# ax12_control_board.net
KiCad netlist of a schematic drawn in EAGLE
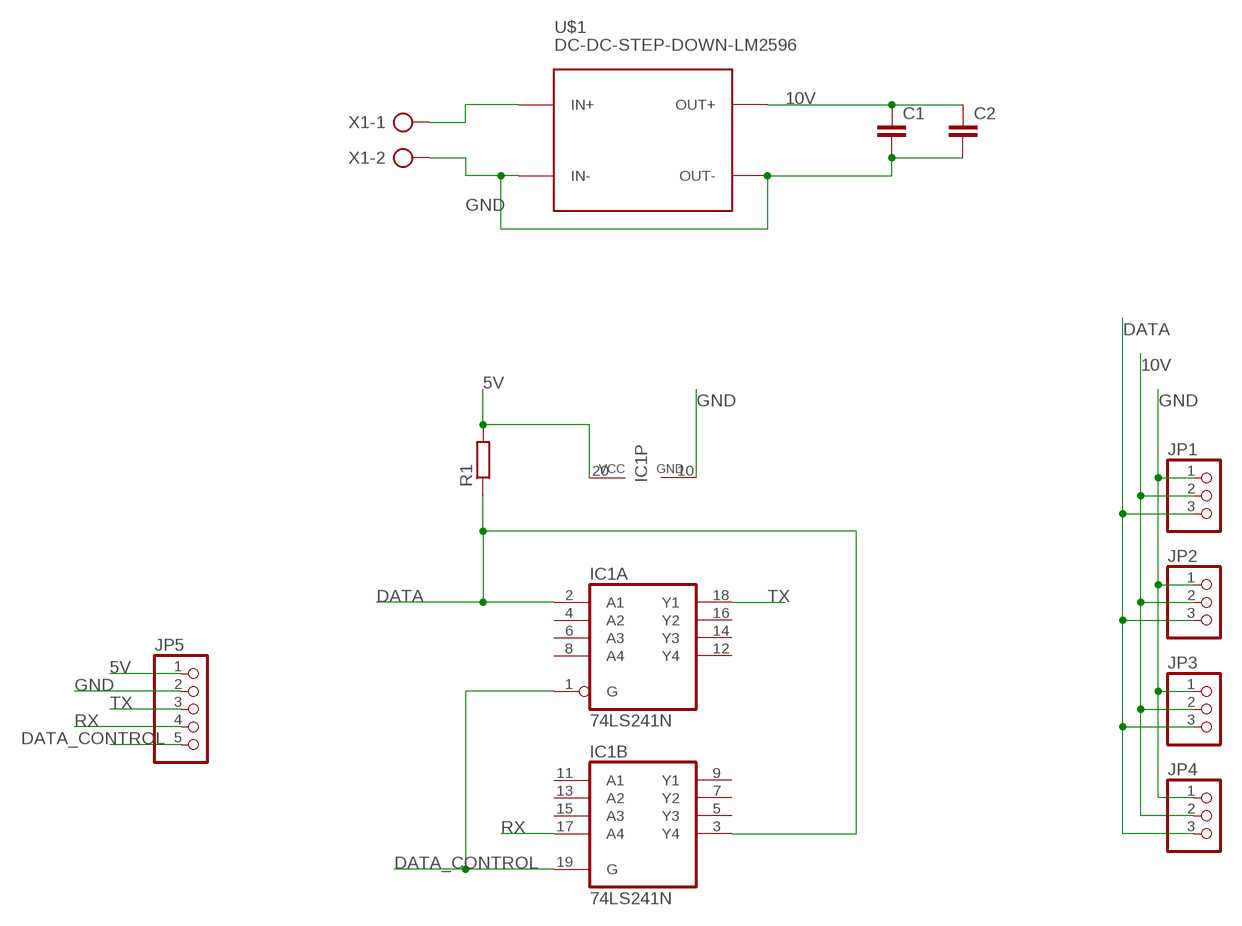
[diagram p0: schematic, sheet 1]

(export (version "E")
  (design (tool "Eeschema 10.0.6"))
  (components
    (comp (ref "C1")
      (value "C-EU025-060X050")
      (footprint "eagle-import:C025-060X050")
      (libsource (lib "eagle-import") (part "C-EU025-060X050"))
    )
    (comp (ref "C2")
      (value "C-EU025-060X050")
      (footprint "eagle-import:C025-060X050")
      (libsource (lib "eagle-import") (part "C-EU025-060X050"))
    )
    (comp (ref "IC1")
      (value "74LS241N")
      (footprint "eagle-import:DIL20")
      (libsource (lib "eagle-import") (part "74241NLS"))
    )
    (comp (ref "JP1")
      (value "PINHD-1X3")
      (footprint "eagle-import:1X03")
      (libsource (lib "eagle-import") (part "PINHD-1X3"))
    )
    (comp (ref "JP2")
      (value "PINHD-1X3")
      (footprint "eagle-import:1X03")
      (libsource (lib "eagle-import") (part "PINHD-1X3"))
    )
    (comp (ref "JP3")
      (value "PINHD-1X3")
      (footprint "eagle-import:1X03")
      (libsource (lib "eagle-import") (part "PINHD-1X3"))
    )
    (comp (ref "JP4")
      (value "PINHD-1X3")
      (footprint "eagle-import:1X03")
      (libsource (lib "eagle-import") (part "PINHD-1X3"))
    )
    (comp (ref "JP5")
      (value "PINHD-1X5")
      (footprint "eagle-import:1X05")
      (libsource (lib "eagle-import") (part "PINHD-1X5"))
    )
    (comp (ref "R1")
      (value "R-EU_0207/12")
      (footprint "eagle-import:0207_12")
      (libsource (lib "eagle-import") (part "R-EU_0207/12"))
    )
    (comp (ref "U$1")
      (value "DC-DC-STEP-DOWN-LM2596")
      (footprint "eagle-import:DC-DC-STEP-DOWN-LM2596")
      (libsource (lib "eagle-import") (part "DC-DC-STEP-DOWN-LM2596"))
    )
    (comp (ref "X1")
      (value "AK300/2")
      (footprint "eagle-import:AK300_2")
      (libsource (lib "eagle-import") (part "AK300/2"))
    )
  )
  (nets
    (net (code "1") (name "/5V") (class "Default")
      (node (ref "IC1") (pin "20") (pinfunction "VCC_20") (pintype "power_in"))
      (node (ref "JP5") (pin "1") (pinfunction "1_1") (pintype "passive"))
      (node (ref "R1") (pin "2") (pinfunction "2_2") (pintype "passive"))
    )
    (net (code "2") (name "/10V") (class "Default")
      (node (ref "C1") (pin "1") (pinfunction "1_1") (pintype "passive"))
      (node (ref "C2") (pin "1") (pinfunction "1_1") (pintype "passive"))
      (node (ref "JP1") (pin "2") (pinfunction "2_2") (pintype "passive"))
      (node (ref "JP2") (pin "2") (pinfunction "2_2") (pintype "passive"))
      (node (ref "JP3") (pin "2") (pinfunction "2_2") (pintype "passive"))
      (node (ref "JP4") (pin "2") (pinfunction "2_2") (pintype "passive"))
      (node (ref "U$1") (pin "OUT+") (pinfunction "OUT+_OUT+") (pintype "bidirectional"))
    )
    (net (code "3") (name "/DATA") (class "Default")
      (node (ref "IC1") (pin "2") (pinfunction "A1_2") (pintype "input"))
      (node (ref "IC1") (pin "3") (pinfunction "Y4_3") (pintype "tri_state"))
      (node (ref "JP1") (pin "3") (pinfunction "3_3") (pintype "passive"))
      (node (ref "JP2") (pin "3") (pinfunction "3_3") (pintype "passive"))
      (node (ref "JP3") (pin "3") (pinfunction "3_3") (pintype "passive"))
      (node (ref "JP4") (pin "3") (pinfunction "3_3") (pintype "passive"))
      (node (ref "R1") (pin "1") (pinfunction "1_1") (pintype "passive"))
    )
    (net (code "4") (name "/DATA_CONTROL") (class "Default")
      (node (ref "IC1") (pin "1") (pinfunction "G_1") (pintype "input"))
      (node (ref "IC1") (pin "19") (pinfunction "G_19") (pintype "input"))
      (node (ref "JP5") (pin "5") (pinfunction "5_5") (pintype "passive"))
    )
    (net (code "5") (name "/GND") (class "Default")
      (node (ref "C1") (pin "2") (pinfunction "2_2") (pintype "passive"))
      (node (ref "C2") (pin "2") (pinfunction "2_2") (pintype "passive"))
      (node (ref "IC1") (pin "10") (pinfunction "GND_10") (pintype "power_in"))
      (node (ref "JP1") (pin "1") (pinfunction "1_1") (pintype "passive"))
      (node (ref "JP2") (pin "1") (pinfunction "1_1") (pintype "passive"))
      (node (ref "JP3") (pin "1") (pinfunction "1_1") (pintype "passive"))
      (node (ref "JP4") (pin "1") (pinfunction "1_1") (pintype "passive"))
      (node (ref "JP5") (pin "2") (pinfunction "2_2") (pintype "passive"))
      (node (ref "U$1") (pin "IN-") (pinfunction "IN-_IN-") (pintype "bidirectional"))
      (node (ref "U$1") (pin "OUT-") (pinfunction "OUT-_OUT-") (pintype "bidirectional"))
      (node (ref "X1") (pin "2") (pinfunction "KL_2") (pintype "passive"))
    )
    (net (code "6") (name "/RX") (class "Default")
      (node (ref "IC1") (pin "17") (pinfunction "A4_17") (pintype "input"))
      (node (ref "JP5") (pin "4") (pinfunction "4_4") (pintype "passive"))
    )
    (net (code "7") (name "/TX") (class "Default")
      (node (ref "IC1") (pin "18") (pinfunction "Y1_18") (pintype "tri_state"))
      (node (ref "JP5") (pin "3") (pinfunction "3_3") (pintype "passive"))
    )
    (net (code "8") (name "Net-(X1A-KL)") (class "Default")
      (node (ref "U$1") (pin "IN+") (pinfunction "IN+_IN+") (pintype "bidirectional"))
      (node (ref "X1") (pin "1") (pinfunction "KL_1") (pintype "passive"))
    )
    (net (code "9") (name "unconnected-(IC1A-A2-Pad4)") (class "Default")
      (node (ref "IC1") (pin "4") (pinfunction "A2_4") (pintype "input"))
    )
    (net (code "10") (name "unconnected-(IC1A-A3-Pad6)") (class "Default")
      (node (ref "IC1") (pin "6") (pinfunction "A3_6") (pintype "input"))
    )
    (net (code "11") (name "unconnected-(IC1A-A4-Pad8)") (class "Default")
      (node (ref "IC1") (pin "8") (pinfunction "A4_8") (pintype "input"))
    )
    (net (code "12") (name "unconnected-(IC1A-Y2-Pad16)") (class "Default")
      (node (ref "IC1") (pin "16") (pinfunction "Y2_16") (pintype "tri_state"))
    )
    (net (code "13") (name "unconnected-(IC1A-Y3-Pad14)") (class "Default")
      (node (ref "IC1") (pin "14") (pinfunction "Y3_14") (pintype "tri_state"))
    )
    (net (code "14") (name "unconnected-(IC1A-Y4-Pad12)") (class "Default")
      (node (ref "IC1") (pin "12") (pinfunction "Y4_12") (pintype "tri_state"))
    )
    (net (code "15") (name "unconnected-(IC1B-A1-Pad11)") (class "Default")
      (node (ref "IC1") (pin "11") (pinfunction "A1_11") (pintype "input"))
    )
    (net (code "16") (name "unconnected-(IC1B-A2-Pad13)") (class "Default")
      (node (ref "IC1") (pin "13") (pinfunction "A2_13") (pintype "input"))
    )
    (net (code "17") (name "unconnected-(IC1B-A3-Pad15)") (class "Default")
      (node (ref "IC1") (pin "15") (pinfunction "A3_15") (pintype "input"))
    )
    (net (code "18") (name "unconnected-(IC1B-Y1-Pad9)") (class "Default")
      (node (ref "IC1") (pin "9") (pinfunction "Y1_9") (pintype "tri_state"))
    )
    (net (code "19") (name "unconnected-(IC1B-Y2-Pad7)") (class "Default")
      (node (ref "IC1") (pin "7") (pinfunction "Y2_7") (pintype "tri_state"))
    )
    (net (code "20") (name "unconnected-(IC1B-Y3-Pad5)") (class "Default")
      (node (ref "IC1") (pin "5") (pinfunction "Y3_5") (pintype "tri_state"))
    )
  )
)
